# Power.net
KiCad netlist of a schematic drawn in Altium Designer
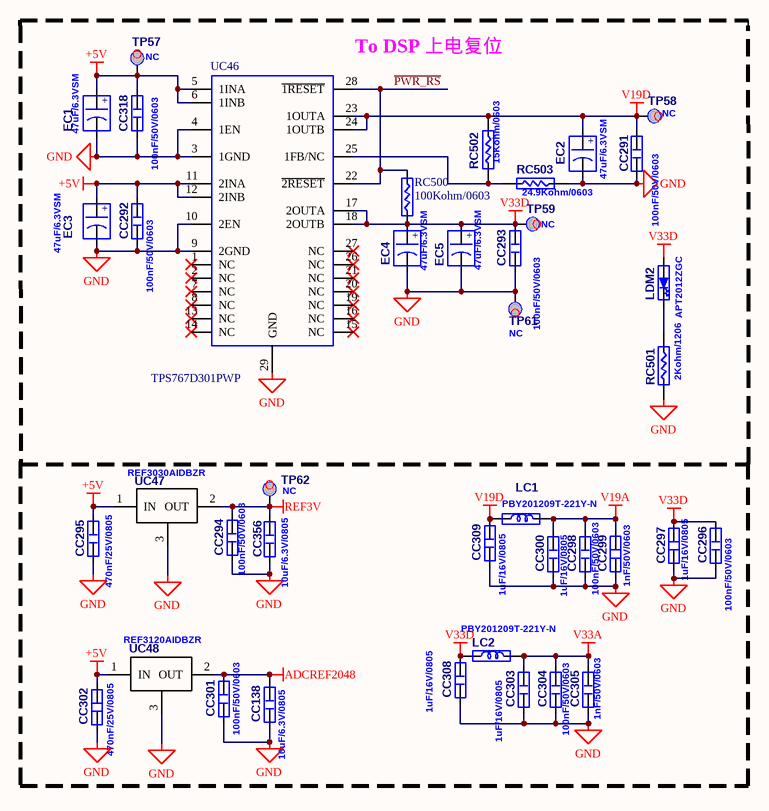
[diagram p0: Power.SchDoc]

(export (version "E")
  (design (tool "Eeschema 10.0.6"))
  (components
    (comp (ref "CC138")
      (value "10uF/6.3V/0805")
      (footprint "CC2012-0805")
      (description "10uF/6.3V/K/X7R/0805")
      (fields (field (name "Comment") "023-106330-0"))
      (libsource (lib "00") (part "C0603 SM"))
    )
    (comp (ref "CC291")
      (value "100nF/50V/0603")
      (footprint "CC1608-0603")
      (description "100nF/50V/J/X7R/0603")
      (fields (field (name "Comment") "023-105220-0"))
      (libsource (lib "00") (part "C0603 SM"))
    )
    (comp (ref "CC292")
      (value "100nF/50V/0603")
      (footprint "CC1608-0603")
      (description "100nF/50V/J/X7R/0603")
      (fields (field (name "Comment") "023-105220-0"))
      (libsource (lib "00") (part "C0603 SM"))
    )
    (comp (ref "CC293")
      (value "100nF/50V/0603")
      (footprint "CC1608-0603")
      (description "100nF/50V/J/X7R/0603")
      (fields (field (name "Comment") "023-105220-0"))
      (libsource (lib "00") (part "C0603 SM"))
    )
    (comp (ref "CC294")
      (value "100nF/50V/0603")
      (footprint "CC1608-0603")
      (description "100nF/50V/J/X7R/0603")
      (fields (field (name "Comment") "023-105220-0"))
      (libsource (lib "00") (part "C0603 SM"))
    )
    (comp (ref "CC295")
      (value "470nF/25V/0805")
      (footprint "CC2012-0805")
      (description "470nF/25V/J/X7R/0805")
      (fields (field (name "Comment") "023-474250-0"))
      (libsource (lib "00") (part "C0805 SM"))
    )
    (comp (ref "CC296")
      (value "100nF/50V/0603")
      (footprint "CC1608-0603")
      (description "100nF/50V/J/X7R/0603")
      (fields (field (name "Comment") "023-105220-0"))
      (libsource (lib "00") (part "C0603 SM"))
    )
    (comp (ref "CC297")
      (value "1uF/16V/0805")
      (footprint "CC2012-0805")
      (description "1uF/16V/K/X7R/0805")
      (fields (field (name "Comment") "023-105330-0"))
      (libsource (lib "00") (part "C0603 SM"))
    )
    (comp (ref "CC298")
      (value "100nF/50V/0603")
      (footprint "CC1608-0603")
      (description "100nF/50V/J/X7R/0603")
      (fields (field (name "Comment") "023-105220-0"))
      (libsource (lib "00") (part "C0603 SM"))
    )
    (comp (ref "CC299")
      (value "1nF/50V/0603")
      (footprint "CC1608-0603")
      (description "1nF/50V/J/C0G/0603")
      (fields (field (name "Comment") "023-102220-0"))
      (libsource (lib "00") (part "C0603 SM"))
    )
    (comp (ref "CC300")
      (value "1uF/16V/0805")
      (footprint "CC2012-0805")
      (description "1uF/16V/K/X7R/0805")
      (fields (field (name "Comment") "023-105330-0"))
      (libsource (lib "00") (part "C0603 SM"))
    )
    (comp (ref "CC301")
      (value "100nF/50V/0603")
      (footprint "CC1608-0603")
      (description "100nF/50V/J/X7R/0603")
      (fields (field (name "Comment") "023-105220-0"))
      (libsource (lib "00") (part "C0603 SM"))
    )
    (comp (ref "CC302")
      (value "470nF/25V/0805")
      (footprint "CC2012-0805")
      (description "470nF/25V/J/X7R/0805")
      (fields (field (name "Comment") "023-474250-0"))
      (libsource (lib "00") (part "C0805 SM"))
    )
    (comp (ref "CC303")
      (value "1uF/16V/0805")
      (footprint "CC2012-0805")
      (description "1uF/16V/K/X7R/0805")
      (fields (field (name "Comment") "023-105330-0"))
      (libsource (lib "00") (part "C0603 SM"))
    )
    (comp (ref "CC304")
      (value "100nF/50V/0603")
      (footprint "CC1608-0603")
      (description "100nF/50V/J/X7R/0603")
      (fields (field (name "Comment") "023-105220-0"))
      (libsource (lib "00") (part "C0603 SM"))
    )
    (comp (ref "CC305")
      (value "1nF/50V/0603")
      (footprint "CC1608-0603")
      (description "1nF/50V/J/C0G/0603")
      (fields (field (name "Comment") "023-102220-0"))
      (libsource (lib "00") (part "C0603 SM"))
    )
    (comp (ref "CC308")
      (value "1uF/16V/0805")
      (footprint "CC2012-0805")
      (description "1uF/16V/K/X7R/0805")
      (fields (field (name "Comment") "023-105330-0"))
      (libsource (lib "00") (part "C0603 SM"))
    )
    (comp (ref "CC309")
      (value "1uF/16V/0805")
      (footprint "CC2012-0805")
      (description "1uF/16V/K/X7R/0805")
      (fields (field (name "Comment") "023-105330-0"))
      (libsource (lib "00") (part "C0603 SM"))
    )
    (comp (ref "CC318")
      (value "100nF/50V/0603")
      (footprint "CC1608-0603")
      (description "100nF/50V/J/X7R/0603")
      (fields (field (name "Comment") "023-105220-0"))
      (libsource (lib "00") (part "C0603 SM"))
    )
    (comp (ref "CC356")
      (value "10uF/6.3V/0805")
      (footprint "CC2012-0805")
      (description "10uF/6.3V/K/X7R/0805")
      (fields (field (name "Comment") "023-106330-0"))
      (libsource (lib "00") (part "C0603 SM"))
    )
    (comp (ref "EC1")
      (value "47uF/6.3VSM")
      (footprint "EC47UF/6.3VSM-5")
      (description "47uF/6.3V/Φ5*7/7000H/CW系列")
      (fields (field (name "Comment") "020-476003-0"))
      (libsource (lib "00") (part "C47U/6.3VSM"))
    )
    (comp (ref "EC2")
      (value "47uF/6.3VSM")
      (footprint "EC47UF/6.3VSM-5")
      (description "47uF/6.3V/Φ5*7/7000H/CW系列")
      (fields (field (name "Comment") "020-476003-0"))
      (libsource (lib "00") (part "C47U/6.3VSM"))
    )
    (comp (ref "EC3")
      (value "47uF/6.3VSM")
      (footprint "EC47UF/6.3VSM-5")
      (description "47uF/6.3V/Φ5*7/7000H/CW系列")
      (fields (field (name "Comment") "020-476003-0"))
      (libsource (lib "00") (part "C47U/6.3VSM"))
    )
    (comp (ref "EC4")
      (value "47uF/6.3VSM")
      (footprint "EC47UF/6.3VSM-5")
      (description "47uF/6.3V/Φ5*7/7000H/CW系列")
      (fields (field (name "Comment") "020-476003-0"))
      (libsource (lib "00") (part "C47U/6.3VSM"))
    )
    (comp (ref "EC5")
      (value "47uF/6.3VSM")
      (footprint "EC47UF/6.3VSM-5")
      (description "47uF/6.3V/Φ5*7/7000H/CW系列")
      (fields (field (name "Comment") "020-476003-0"))
      (libsource (lib "00") (part "C47U/6.3VSM"))
    )
    (comp (ref "LC1")
      (value "PBY201209T-221Y-N")
      (footprint "L2012-0805")
      (description "220Ω±25%/100MHZ/20℃/0805")
      (fields (field (name "Comment") "080-200001-0"))
      (libsource (lib "00") (part "L0805SM"))
    )
    (comp (ref "LC2")
      (value "PBY201209T-221Y-N")
      (footprint "L2012-0805")
      (description "220Ω±25%/100MHZ/20℃/0805")
      (fields (field (name "Comment") "080-200001-0"))
      (libsource (lib "00") (part "L0805SM"))
    )
    (comp (ref "LDM2")
      (value "APT2012ZGC")
      (footprint "LED2012-0805SM")
      (description "2.0*1.25*0.75mm/Green")
      (fields (field (name "Comment") "060-011000-0"))
      (libsource (lib "00") (part "LD0805SM"))
    )
    (comp (ref "RC500")
      (value "100Kohm/0603")
      (footprint "R0603SM")
      (description "100Kohm/1/10W/F/0603")
      (fields (field (name "Comment") "011-104020-0"))
      (libsource (lib "首航") (part "011-104020-0 R0603SM"))
    )
    (comp (ref "RC501")
      (value "2Kohm/1206")
      (footprint "R3216-1206")
      (description "2Kohm/1/4W/F/1206")
      (fields (field (name "Comment") "011-202050-0"))
      (libsource (lib "00") (part "R1206SM"))
    )
    (comp (ref "RC502")
      (value "15Kohm/0603")
      (footprint "R1608-0603")
      (description "15Kohm/1/10W/F/0603")
      (fields (field (name "Comment") "011-153020-0"))
      (libsource (lib "00") (part "R0603SM"))
    )
    (comp (ref "RC503")
      (value "24.9Kohm/0603")
      (footprint "R1608-0603")
      (description "24.9Kohm/1/10W/F/0603")
      (fields (field (name "Comment") "011-243020-0"))
      (libsource (lib "00") (part "R0603SM"))
    )
    (comp (ref "TP57") (value "NC") (footprint "TEST-12") (libsource (lib "00") (part "17K TPD")))
    (comp (ref "TP58") (value "NC") (footprint "TEST-12") (libsource (lib "00") (part "17K TPD")))
    (comp (ref "TP59") (value "NC") (footprint "TEST-12") (libsource (lib "00") (part "17K TPD")))
    (comp (ref "TP61") (value "NC") (footprint "TEST-12") (libsource (lib "00") (part "17K TPD")))
    (comp (ref "TP62") (value "NC") (footprint "TEST-12") (libsource (lib "00") (part "17K TPD")))
    (comp (ref "UC46")
      (value "TPS767D301PWP")
      (footprint "TSSOP28-9.8X4.5-PD")
      (description "Low Dropout Regulator/HTSSOP-28")
      (fields (field (name "Comment") "050-210100-0"))
      (libsource (lib "首航") (part "050-210100-0 TSSOP28-9.8X4.5-PD"))
    )
    (comp (ref "UC47")
      (value "REF3030AIDBZR")
      (footprint "SOT-23")
      (description "Voltage Reference/SOT23-3")
      (fields (field (name "Comment") "050-210111-0"))
      (libsource (lib "00") (part "SOT-23SM"))
    )
    (comp (ref "UC48")
      (value "REF3120AIDBZR")
      (footprint "SOT23-3")
      (description "Voltage Reference/SOT23-3")
      (fields (field (name "Comment") "050-210120-0"))
      (libsource (lib "00") (part "SOT23-3"))
    )
  )
  (nets
    (net (code "1") (name "+5V") (class "Default")
      (node (ref "CC292") (pin "2") (pinfunction "2_2") (pintype "passive"))
      (node (ref "CC295") (pin "1") (pinfunction "1_1") (pintype "passive"))
      (node (ref "CC302") (pin "1") (pinfunction "1_1") (pintype "passive"))
      (node (ref "CC318") (pin "2") (pinfunction "2_2") (pintype "passive"))
      (node (ref "EC1") (pin "1") (pinfunction "1_1") (pintype "passive"))
      (node (ref "EC3") (pin "1") (pinfunction "1_1") (pintype "passive"))
      (node (ref "TP57") (pin "1") (pinfunction "1_1") (pintype "passive"))
      (node (ref "UC46") (pin "11") (pinfunction "2INA_11") (pintype "passive"))
      (node (ref "UC46") (pin "12") (pinfunction "2INB_12") (pintype "passive"))
      (node (ref "UC46") (pin "5") (pinfunction "1INA_5") (pintype "passive"))
      (node (ref "UC46") (pin "6") (pinfunction "1INB_6") (pintype "passive"))
      (node (ref "UC47") (pin "1") (pinfunction "IN_1") (pintype "passive"))
      (node (ref "UC48") (pin "1") (pinfunction "IN_1") (pintype "passive"))
    )
    (net (code "2") (name "/~{PWR_RS}") (class "Default")
      (node (ref "RC500") (pin "2") (pinfunction "2_2") (pintype "passive"))
      (node (ref "UC46") (pin "22") (pinfunction "~{2RESET}_22") (pintype "passive"))
      (node (ref "UC46") (pin "28") (pinfunction "~{1RESET}_28") (pintype "passive"))
    )
    (net (code "3") (name "ADCREF2048") (class "Default")
      (node (ref "CC138") (pin "2") (pinfunction "2_2") (pintype "passive"))
      (node (ref "CC301") (pin "1") (pinfunction "1_1") (pintype "passive"))
      (node (ref "UC48") (pin "2") (pinfunction "OUT_2") (pintype "passive"))
    )
    (net (code "4") (name "GND") (class "Default")
      (node (ref "CC138") (pin "1") (pinfunction "1_1") (pintype "passive"))
      (node (ref "CC291") (pin "2") (pinfunction "2_2") (pintype "passive"))
      (node (ref "CC292") (pin "1") (pinfunction "1_1") (pintype "passive"))
      (node (ref "CC293") (pin "2") (pinfunction "2_2") (pintype "passive"))
      (node (ref "CC294") (pin "2") (pinfunction "2_2") (pintype "passive"))
      (node (ref "CC295") (pin "2") (pinfunction "2_2") (pintype "passive"))
      (node (ref "CC296") (pin "2") (pinfunction "2_2") (pintype "passive"))
      (node (ref "CC297") (pin "1") (pinfunction "1_1") (pintype "passive"))
      (node (ref "CC298") (pin "2") (pinfunction "2_2") (pintype "passive"))
      (node (ref "CC299") (pin "2") (pinfunction "2_2") (pintype "passive"))
      (node (ref "CC300") (pin "2") (pinfunction "2_2") (pintype "passive"))
      (node (ref "CC301") (pin "2") (pinfunction "2_2") (pintype "passive"))
      (node (ref "CC302") (pin "2") (pinfunction "2_2") (pintype "passive"))
      (node (ref "CC303") (pin "1") (pinfunction "1_1") (pintype "passive"))
      (node (ref "CC304") (pin "2") (pinfunction "2_2") (pintype "passive"))
      (node (ref "CC305") (pin "1") (pinfunction "1_1") (pintype "passive"))
      (node (ref "CC308") (pin "1") (pinfunction "1_1") (pintype "passive"))
      (node (ref "CC309") (pin "1") (pinfunction "1_1") (pintype "passive"))
      (node (ref "CC318") (pin "1") (pinfunction "1_1") (pintype "passive"))
      (node (ref "CC356") (pin "1") (pinfunction "1_1") (pintype "passive"))
      (node (ref "EC1") (pin "2") (pinfunction "2_2") (pintype "passive"))
      (node (ref "EC2") (pin "2") (pinfunction "2_2") (pintype "passive"))
      (node (ref "EC3") (pin "2") (pinfunction "2_2") (pintype "passive"))
      (node (ref "EC4") (pin "2") (pinfunction "2_2") (pintype "passive"))
      (node (ref "EC5") (pin "2") (pinfunction "2_2") (pintype "passive"))
      (node (ref "RC501") (pin "1") (pinfunction "1_1") (pintype "passive"))
      (node (ref "RC503") (pin "1") (pinfunction "1_1") (pintype "passive"))
      (node (ref "TP61") (pin "1") (pinfunction "1_1") (pintype "passive"))
      (node (ref "UC46") (pin "10") (pinfunction "2EN_10") (pintype "passive"))
      (node (ref "UC46") (pin "29") (pinfunction "GND_29") (pintype "passive"))
      (node (ref "UC46") (pin "3") (pinfunction "1GND_3") (pintype "passive"))
      (node (ref "UC46") (pin "4") (pinfunction "1EN_4") (pintype "passive"))
      (node (ref "UC46") (pin "9") (pinfunction "2GND_9") (pintype "passive"))
      (node (ref "UC47") (pin "3") (pintype "passive"))
      (node (ref "UC48") (pin "3") (pintype "passive"))
    )
    (net (code "5") (name "Net-(LDM2-Pad2)") (class "Default")
      (node (ref "LDM2") (pin "2") (pinfunction "2_2") (pintype "passive"))
      (node (ref "RC501") (pin "2") (pinfunction "2_2") (pintype "passive"))
    )
    (net (code "6") (name "Net-(UC46-1FB{slash}NC)") (class "Default")
      (node (ref "RC502") (pin "1") (pinfunction "1_1") (pintype "passive"))
      (node (ref "RC503") (pin "2") (pinfunction "2_2") (pintype "passive"))
      (node (ref "UC46") (pin "25") (pinfunction "1FB/NC_25") (pintype "passive"))
    )
    (net (code "7") (name "REF3V") (class "Default")
      (node (ref "CC294") (pin "1") (pinfunction "1_1") (pintype "passive"))
      (node (ref "CC356") (pin "2") (pinfunction "2_2") (pintype "passive"))
      (node (ref "TP62") (pin "1") (pinfunction "1_1") (pintype "passive"))
      (node (ref "UC47") (pin "2") (pinfunction "OUT_2") (pintype "passive"))
    )
    (net (code "8") (name "V19A") (class "Default")
      (node (ref "CC298") (pin "1") (pinfunction "1_1") (pintype "passive"))
      (node (ref "CC299") (pin "1") (pinfunction "1_1") (pintype "passive"))
      (node (ref "CC300") (pin "1") (pinfunction "1_1") (pintype "passive"))
      (node (ref "LC1") (pin "2") (pinfunction "2_2") (pintype "passive"))
    )
    (net (code "9") (name "V19D") (class "Default")
      (node (ref "CC291") (pin "1") (pinfunction "1_1") (pintype "passive"))
      (node (ref "CC309") (pin "2") (pinfunction "2_2") (pintype "passive"))
      (node (ref "EC2") (pin "1") (pinfunction "1_1") (pintype "passive"))
      (node (ref "LC1") (pin "1") (pinfunction "1_1") (pintype "passive"))
      (node (ref "RC502") (pin "2") (pinfunction "2_2") (pintype "passive"))
      (node (ref "TP58") (pin "1") (pinfunction "1_1") (pintype "passive"))
      (node (ref "UC46") (pin "23") (pinfunction "1OUTA_23") (pintype "passive"))
      (node (ref "UC46") (pin "24") (pinfunction "1OUTB_24") (pintype "passive"))
    )
    (net (code "10") (name "V33A") (class "Default")
      (node (ref "CC303") (pin "2") (pinfunction "2_2") (pintype "passive"))
      (node (ref "CC304") (pin "1") (pinfunction "1_1") (pintype "passive"))
      (node (ref "CC305") (pin "2") (pinfunction "2_2") (pintype "passive"))
      (node (ref "LC2") (pin "2") (pinfunction "2_2") (pintype "passive"))
    )
    (net (code "11") (name "V33D") (class "Default")
      (node (ref "CC293") (pin "1") (pinfunction "1_1") (pintype "passive"))
      (node (ref "CC296") (pin "1") (pinfunction "1_1") (pintype "passive"))
      (node (ref "CC297") (pin "2") (pinfunction "2_2") (pintype "passive"))
      (node (ref "CC308") (pin "2") (pinfunction "2_2") (pintype "passive"))
      (node (ref "EC4") (pin "1") (pinfunction "1_1") (pintype "passive"))
      (node (ref "EC5") (pin "1") (pinfunction "1_1") (pintype "passive"))
      (node (ref "LC2") (pin "1") (pinfunction "1_1") (pintype "passive"))
      (node (ref "LDM2") (pin "1") (pinfunction "1_1") (pintype "passive"))
      (node (ref "RC500") (pin "1") (pinfunction "1_1") (pintype "passive"))
      (node (ref "TP59") (pin "1") (pinfunction "1_1") (pintype "passive"))
      (node (ref "UC46") (pin "17") (pinfunction "2OUTA_17") (pintype "passive"))
      (node (ref "UC46") (pin "18") (pinfunction "2OUTB_18") (pintype "passive"))
    )
    (net (code "12") (name "unconnected-(UC46-NC-Pad1)") (class "Default")
      (node (ref "UC46") (pin "1") (pinfunction "NC_1") (pintype "passive+no_connect"))
    )
    (net (code "13") (name "unconnected-(UC46-NC-Pad2)") (class "Default")
      (node (ref "UC46") (pin "2") (pinfunction "NC_2") (pintype "passive+no_connect"))
    )
    (net (code "14") (name "unconnected-(UC46-NC-Pad7)") (class "Default")
      (node (ref "UC46") (pin "7") (pinfunction "NC_7") (pintype "passive+no_connect"))
    )
    (net (code "15") (name "unconnected-(UC46-NC-Pad8)") (class "Default")
      (node (ref "UC46") (pin "8") (pinfunction "NC_8") (pintype "passive+no_connect"))
    )
    (net (code "16") (name "unconnected-(UC46-NC-Pad13)") (class "Default")
      (node (ref "UC46") (pin "13") (pinfunction "NC_13") (pintype "passive+no_connect"))
    )
    (net (code "17") (name "unconnected-(UC46-NC-Pad14)") (class "Default")
      (node (ref "UC46") (pin "14") (pinfunction "NC_14") (pintype "passive+no_connect"))
    )
    (net (code "18") (name "unconnected-(UC46-NC-Pad15)") (class "Default")
      (node (ref "UC46") (pin "15") (pinfunction "NC_15") (pintype "passive+no_connect"))
    )
    (net (code "19") (name "unconnected-(UC46-NC-Pad16)") (class "Default")
      (node (ref "UC46") (pin "16") (pinfunction "NC_16") (pintype "passive+no_connect"))
    )
    (net (code "20") (name "unconnected-(UC46-NC-Pad19)") (class "Default")
      (node (ref "UC46") (pin "19") (pinfunction "NC_19") (pintype "passive+no_connect"))
    )
    (net (code "21") (name "unconnected-(UC46-NC-Pad20)") (class "Default")
      (node (ref "UC46") (pin "20") (pinfunction "NC_20") (pintype "passive+no_connect"))
    )
    (net (code "22") (name "unconnected-(UC46-NC-Pad21)") (class "Default")
      (node (ref "UC46") (pin "21") (pinfunction "NC_21") (pintype "passive+no_connect"))
    )
    (net (code "23") (name "unconnected-(UC46-NC-Pad26)") (class "Default")
      (node (ref "UC46") (pin "26") (pinfunction "NC_26") (pintype "passive+no_connect"))
    )
    (net (code "24") (name "unconnected-(UC46-NC-Pad27)") (class "Default")
      (node (ref "UC46") (pin "27") (pinfunction "NC_27") (pintype "passive+no_connect"))
    )
  )
)
